# Sh_Alims.net
KiCad netlist of a schematic drawn in Altium Designer
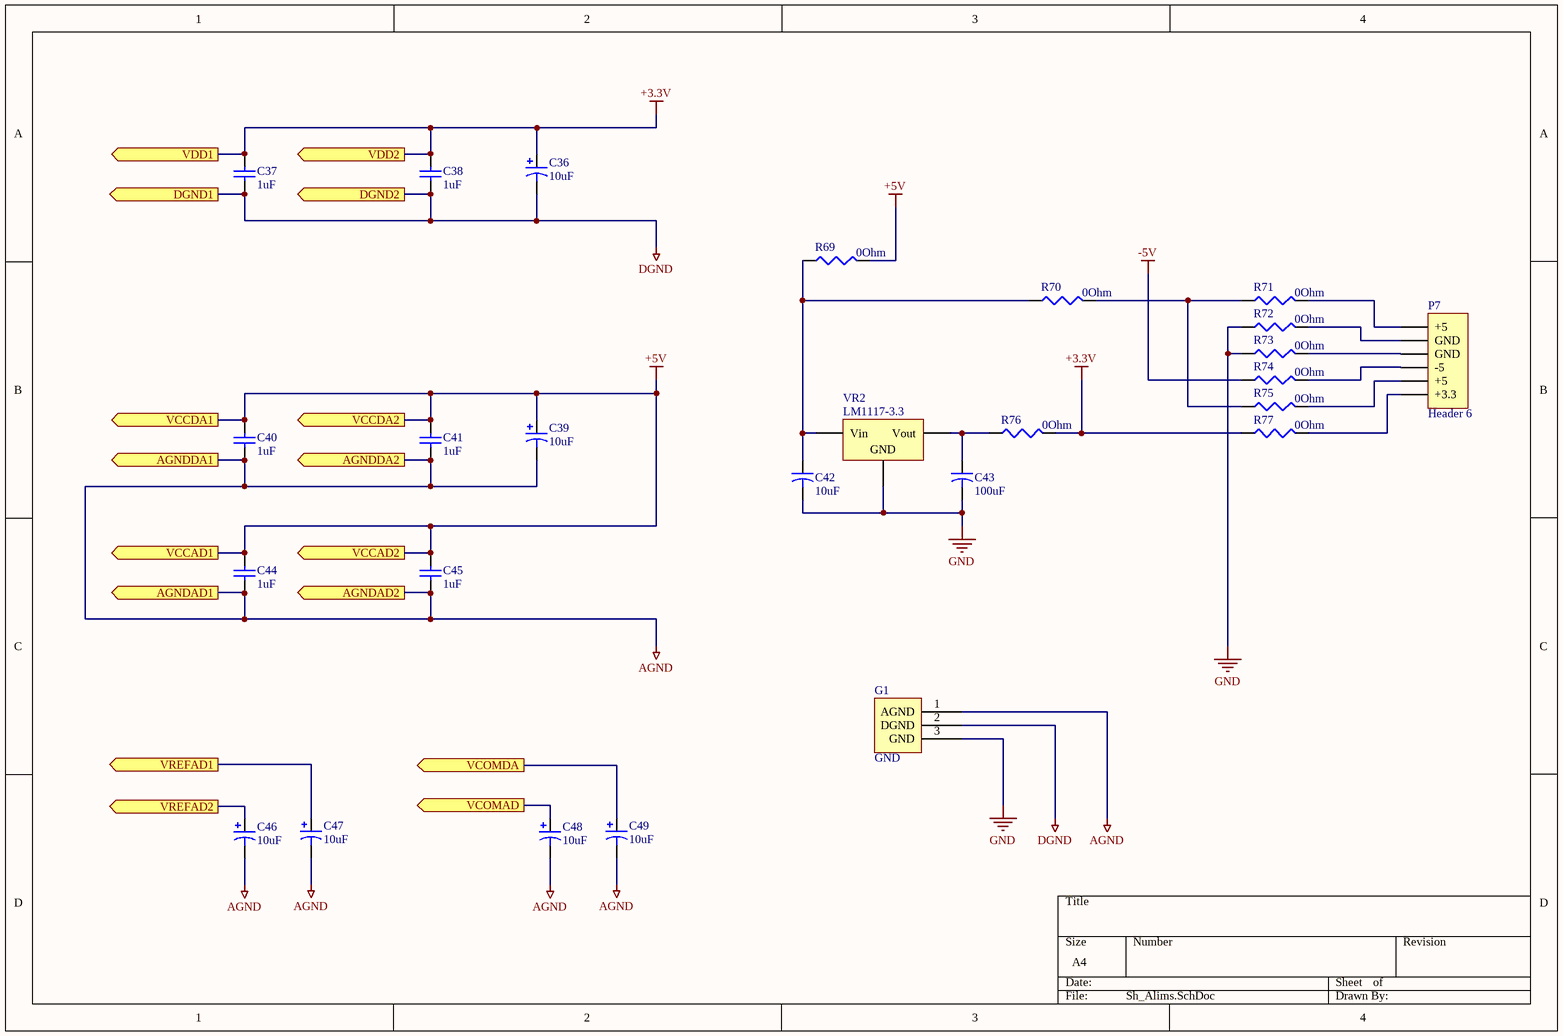
[diagram p0: Sh_Alims.SchDoc]

(export (version "E")
  (design (tool "Eeschema 10.0.6"))
  (components
    (comp (ref "C36")
      (value "10uF")
      (footprint "Cd_elec")
      (description "Polarized Capacitor (Surface Mount)")
      (fields (field (name "Comment") "Cap Pol3") (field (name "PUBLISHER") "Altium Limited"))
      (libsource (lib "Miscellaneous Devices") (part "Cap Pol3"))
    )
    (comp (ref "C37")
      (value "1uF")
      (footprint "1608[0603]")
      (description "Capacitor (Semiconductor SIM Model)")
      (fields (field (name "Comment") "Cap Semi") (field (name "PUBLISHER") "Altium Limited"))
      (libsource (lib "Miscellaneous Devices") (part "Cap Semi"))
    )
    (comp (ref "C38")
      (value "1uF")
      (footprint "1608[0603]")
      (description "Capacitor (Semiconductor SIM Model)")
      (fields (field (name "Comment") "Cap Semi") (field (name "PUBLISHER") "Altium Limited"))
      (libsource (lib "Miscellaneous Devices") (part "Cap Semi"))
    )
    (comp (ref "C39")
      (value "10uF")
      (footprint "Cd_elec")
      (description "Polarized Capacitor (Surface Mount)")
      (fields (field (name "Comment") "Cap Pol3") (field (name "PUBLISHER") "Altium Limited"))
      (libsource (lib "Miscellaneous Devices") (part "Cap Pol3"))
    )
    (comp (ref "C40")
      (value "1uF")
      (footprint "1608[0603]")
      (description "Capacitor (Semiconductor SIM Model)")
      (fields (field (name "Comment") "Cap Semi") (field (name "PUBLISHER") "Altium Limited"))
      (libsource (lib "Miscellaneous Devices") (part "Cap Semi"))
    )
    (comp (ref "C41")
      (value "1uF")
      (footprint "1608[0603]")
      (description "Capacitor (Semiconductor SIM Model)")
      (fields (field (name "Comment") "Cap Semi") (field (name "PUBLISHER") "Altium Limited"))
      (libsource (lib "Miscellaneous Devices") (part "Cap Semi"))
    )
    (comp (ref "C42")
      (value "10uF")
      (footprint "CAPR5-4X5")
      (description "Capacitor")
      (fields (field (name "PUBLISHER") "Altium Limited"))
      (libsource (lib "Miscellaneous Devices") (part "Cap2"))
    )
    (comp (ref "C43")
      (value "100uF")
      (footprint "CAPR5-4X5")
      (description "Capacitor")
      (fields (field (name "PUBLISHER") "Altium Limited"))
      (libsource (lib "Miscellaneous Devices") (part "Cap2"))
    )
    (comp (ref "C44")
      (value "1uF")
      (footprint "1608[0603]")
      (description "Capacitor (Semiconductor SIM Model)")
      (fields (field (name "Comment") "Cap Semi") (field (name "PUBLISHER") "Altium Limited"))
      (libsource (lib "Miscellaneous Devices") (part "Cap Semi"))
    )
    (comp (ref "C45")
      (value "1uF")
      (footprint "1608[0603]")
      (description "Capacitor (Semiconductor SIM Model)")
      (fields (field (name "Comment") "Cap Semi") (field (name "PUBLISHER") "Altium Limited"))
      (libsource (lib "Miscellaneous Devices") (part "Cap Semi"))
    )
    (comp (ref "C46")
      (value "10uF")
      (footprint "Cd_elec")
      (description "Polarized Capacitor (Surface Mount)")
      (fields (field (name "Comment") "Cap Pol3") (field (name "PUBLISHER") "Altium Limited"))
      (libsource (lib "Miscellaneous Devices") (part "Cap Pol3"))
    )
    (comp (ref "C47")
      (value "10uF")
      (footprint "Cd_elec")
      (description "Polarized Capacitor (Surface Mount)")
      (fields (field (name "Comment") "Cap Pol3") (field (name "PUBLISHER") "Altium Limited"))
      (libsource (lib "Miscellaneous Devices") (part "Cap Pol3"))
    )
    (comp (ref "C48")
      (value "10uF")
      (footprint "Cd_elec")
      (description "Polarized Capacitor (Surface Mount)")
      (fields (field (name "Comment") "Cap Pol3") (field (name "PUBLISHER") "Altium Limited"))
      (libsource (lib "Miscellaneous Devices") (part "Cap Pol3"))
    )
    (comp (ref "C49")
      (value "10uF")
      (footprint "Cd_elec")
      (description "Polarized Capacitor (Surface Mount)")
      (fields (field (name "Comment") "Cap Pol3") (field (name "PUBLISHER") "Altium Limited"))
      (libsource (lib "Miscellaneous Devices") (part "Cap Pol3"))
    )
    (comp (ref "G1") (value "GND") (footprint "GND") (libsource (lib "Bonjour") (part "GND")))
    (comp (ref "P7")
      (value "Header 6")
      (footprint "HDR1X6")
      (description "Header, 6-Pin")
      (fields (field (name "PUBLISHER") "Altium Limited"))
      (libsource (lib "Miscellaneous Connectors") (part "Header 6"))
    )
    (comp (ref "R69")
      (value "0Ohm")
      (footprint "J1-0603")
      (description "Resistor")
      (fields (field (name "Comment") "Res3") (field (name "PUBLISHER") "Altium Limited"))
      (libsource (lib "Miscellaneous Devices") (part "Res3"))
    )
    (comp (ref "R70")
      (value "0Ohm")
      (footprint "J1-0603")
      (description "Resistor")
      (fields (field (name "Comment") "Res3") (field (name "PUBLISHER") "Altium Limited"))
      (libsource (lib "Miscellaneous Devices") (part "Res3"))
    )
    (comp (ref "R71")
      (value "0Ohm")
      (footprint "J1-0603")
      (description "Resistor")
      (fields (field (name "Comment") "Res3") (field (name "PUBLISHER") "Altium Limited"))
      (libsource (lib "Miscellaneous Devices") (part "Res3"))
    )
    (comp (ref "R72")
      (value "0Ohm")
      (footprint "J1-0603")
      (description "Resistor")
      (fields (field (name "Comment") "Res3") (field (name "PUBLISHER") "Altium Limited"))
      (libsource (lib "Miscellaneous Devices") (part "Res3"))
    )
    (comp (ref "R73")
      (value "0Ohm")
      (footprint "J1-0603")
      (description "Resistor")
      (fields (field (name "Comment") "Res3") (field (name "PUBLISHER") "Altium Limited"))
      (libsource (lib "Miscellaneous Devices") (part "Res3"))
    )
    (comp (ref "R74")
      (value "0Ohm")
      (footprint "J1-0603")
      (description "Resistor")
      (fields (field (name "Comment") "Res3") (field (name "PUBLISHER") "Altium Limited"))
      (libsource (lib "Miscellaneous Devices") (part "Res3"))
    )
    (comp (ref "R75")
      (value "0Ohm")
      (footprint "J1-0603")
      (description "Resistor")
      (fields (field (name "Comment") "Res3") (field (name "PUBLISHER") "Altium Limited"))
      (libsource (lib "Miscellaneous Devices") (part "Res3"))
    )
    (comp (ref "R76")
      (value "0Ohm")
      (footprint "J1-0603")
      (description "Resistor")
      (fields (field (name "Comment") "Res3") (field (name "PUBLISHER") "Altium Limited"))
      (libsource (lib "Miscellaneous Devices") (part "Res3"))
    )
    (comp (ref "R77")
      (value "0Ohm")
      (footprint "J1-0603")
      (description "Resistor")
      (fields (field (name "Comment") "Res3") (field (name "PUBLISHER") "Altium Limited"))
      (libsource (lib "Miscellaneous Devices") (part "Res3"))
    )
    (comp (ref "VR2")
      (value "LM1117-3.3")
      (footprint "D2PAK_N")
      (description "Voltage Regulator")
      (fields (field (name "PUBLISHER") "Altium Limited"))
      (libsource (lib "Miscellaneous Devices") (part "Volt Reg"))
    )
  )
  (nets
    (net (code "1") (name "+3.3V") (class "Default")
      (node (ref "C36") (pin "1") (pinfunction "1_1") (pintype "passive"))
      (node (ref "C37") (pin "2") (pinfunction "2_2") (pintype "passive"))
      (node (ref "C38") (pin "2") (pinfunction "2_2") (pintype "passive"))
      (node (ref "R76") (pin "2") (pinfunction "2_2") (pintype "passive"))
      (node (ref "R77") (pin "1") (pinfunction "1_1") (pintype "passive"))
    )
    (net (code "2") (name "+5V") (class "Default")
      (node (ref "C39") (pin "1") (pinfunction "1_1") (pintype "passive"))
      (node (ref "C40") (pin "2") (pinfunction "2_2") (pintype "passive"))
      (node (ref "C41") (pin "2") (pinfunction "2_2") (pintype "passive"))
      (node (ref "C44") (pin "2") (pinfunction "2_2") (pintype "passive"))
      (node (ref "C45") (pin "2") (pinfunction "2_2") (pintype "passive"))
      (node (ref "R69") (pin "2") (pinfunction "2_2") (pintype "passive"))
    )
    (net (code "3") (name "-5V") (class "Default")
      (node (ref "R74") (pin "1") (pinfunction "1_1") (pintype "passive"))
    )
    (net (code "4") (name "/VCOMAD") (class "Default")
      (node (ref "C48") (pin "1") (pinfunction "1_1") (pintype "passive"))
    )
    (net (code "5") (name "/VCOMDA") (class "Default")
      (node (ref "C49") (pin "1") (pinfunction "1_1") (pintype "passive"))
    )
    (net (code "6") (name "/VREFAD1") (class "Default")
      (node (ref "C47") (pin "1") (pinfunction "1_1") (pintype "passive"))
    )
    (net (code "7") (name "/VREFAD2") (class "Default")
      (node (ref "C46") (pin "1") (pinfunction "1_1") (pintype "passive"))
    )
    (net (code "8") (name "AGND") (class "Default")
      (node (ref "C39") (pin "2") (pinfunction "2_2") (pintype "passive"))
      (node (ref "C40") (pin "1") (pinfunction "1_1") (pintype "passive"))
      (node (ref "C41") (pin "1") (pinfunction "1_1") (pintype "passive"))
      (node (ref "C44") (pin "1") (pinfunction "1_1") (pintype "passive"))
      (node (ref "C45") (pin "1") (pinfunction "1_1") (pintype "passive"))
      (node (ref "C46") (pin "2") (pinfunction "2_2") (pintype "passive"))
      (node (ref "C47") (pin "2") (pinfunction "2_2") (pintype "passive"))
      (node (ref "C48") (pin "2") (pinfunction "2_2") (pintype "passive"))
      (node (ref "C49") (pin "2") (pinfunction "2_2") (pintype "passive"))
      (node (ref "G1") (pin "1") (pinfunction "AGND_1") (pintype "passive"))
    )
    (net (code "9") (name "DGND") (class "Default")
      (node (ref "C36") (pin "2") (pinfunction "2_2") (pintype "passive"))
      (node (ref "C37") (pin "1") (pinfunction "1_1") (pintype "passive"))
      (node (ref "C38") (pin "1") (pinfunction "1_1") (pintype "passive"))
      (node (ref "G1") (pin "2") (pinfunction "DGND_2") (pintype "passive"))
    )
    (net (code "10") (name "GND") (class "Default")
      (node (ref "C42") (pin "2") (pinfunction "2_2") (pintype "passive"))
      (node (ref "C43") (pin "2") (pinfunction "2_2") (pintype "passive"))
      (node (ref "G1") (pin "3") (pinfunction "GND_3") (pintype "passive"))
      (node (ref "R72") (pin "1") (pinfunction "1_1") (pintype "passive"))
      (node (ref "R73") (pin "1") (pinfunction "1_1") (pintype "passive"))
      (node (ref "VR2") (pin "2") (pinfunction "GND_2") (pintype "passive"))
    )
    (net (code "11") (name "Net-(P7-+3.3)") (class "Default")
      (node (ref "P7") (pin "6") (pinfunction "+3.3_6") (pintype "passive"))
      (node (ref "R77") (pin "2") (pinfunction "2_2") (pintype "passive"))
    )
    (net (code "12") (name "Net-(P7-+5-Pad1)") (class "Default")
      (node (ref "P7") (pin "1") (pinfunction "+5_1") (pintype "passive"))
      (node (ref "R71") (pin "2") (pinfunction "2_2") (pintype "passive"))
    )
    (net (code "13") (name "Net-(P7-+5-Pad5)") (class "Default")
      (node (ref "P7") (pin "5") (pinfunction "+5_5") (pintype "passive"))
      (node (ref "R75") (pin "2") (pinfunction "2_2") (pintype "passive"))
    )
    (net (code "14") (name "Net-(P7--5)") (class "Default")
      (node (ref "P7") (pin "4") (pinfunction "-5_4") (pintype "passive"))
      (node (ref "R74") (pin "2") (pinfunction "2_2") (pintype "passive"))
    )
    (net (code "15") (name "Net-(P7-GND-Pad2)") (class "Default")
      (node (ref "P7") (pin "2") (pinfunction "GND_2") (pintype "passive"))
      (node (ref "R72") (pin "2") (pinfunction "2_2") (pintype "passive"))
    )
    (net (code "16") (name "Net-(P7-GND-Pad3)") (class "Default")
      (node (ref "P7") (pin "3") (pinfunction "GND_3") (pintype "passive"))
      (node (ref "R73") (pin "2") (pinfunction "2_2") (pintype "passive"))
    )
    (net (code "17") (name "Net-(R70-Pad2)") (class "Default")
      (node (ref "R70") (pin "2") (pinfunction "2_2") (pintype "passive"))
      (node (ref "R71") (pin "1") (pinfunction "1_1") (pintype "passive"))
      (node (ref "R75") (pin "1") (pinfunction "1_1") (pintype "passive"))
    )
    (net (code "18") (name "Net-(VR2-Vin)") (class "Default")
      (node (ref "C42") (pin "1") (pinfunction "1_1") (pintype "passive"))
      (node (ref "R69") (pin "1") (pinfunction "1_1") (pintype "passive"))
      (node (ref "R70") (pin "1") (pinfunction "1_1") (pintype "passive"))
      (node (ref "VR2") (pin "1") (pinfunction "Vin_1") (pintype "passive"))
    )
    (net (code "19") (name "Net-(VR2-Vout)") (class "Default")
      (node (ref "C43") (pin "1") (pinfunction "1_1") (pintype "passive"))
      (node (ref "R76") (pin "1") (pinfunction "1_1") (pintype "passive"))
      (node (ref "VR2") (pin "3") (pinfunction "Vout_3") (pintype "passive"))
    )
  )
)
